# CH32V303RCT6-R1.net
KiCad netlist of a schematic drawn in Altium Designer
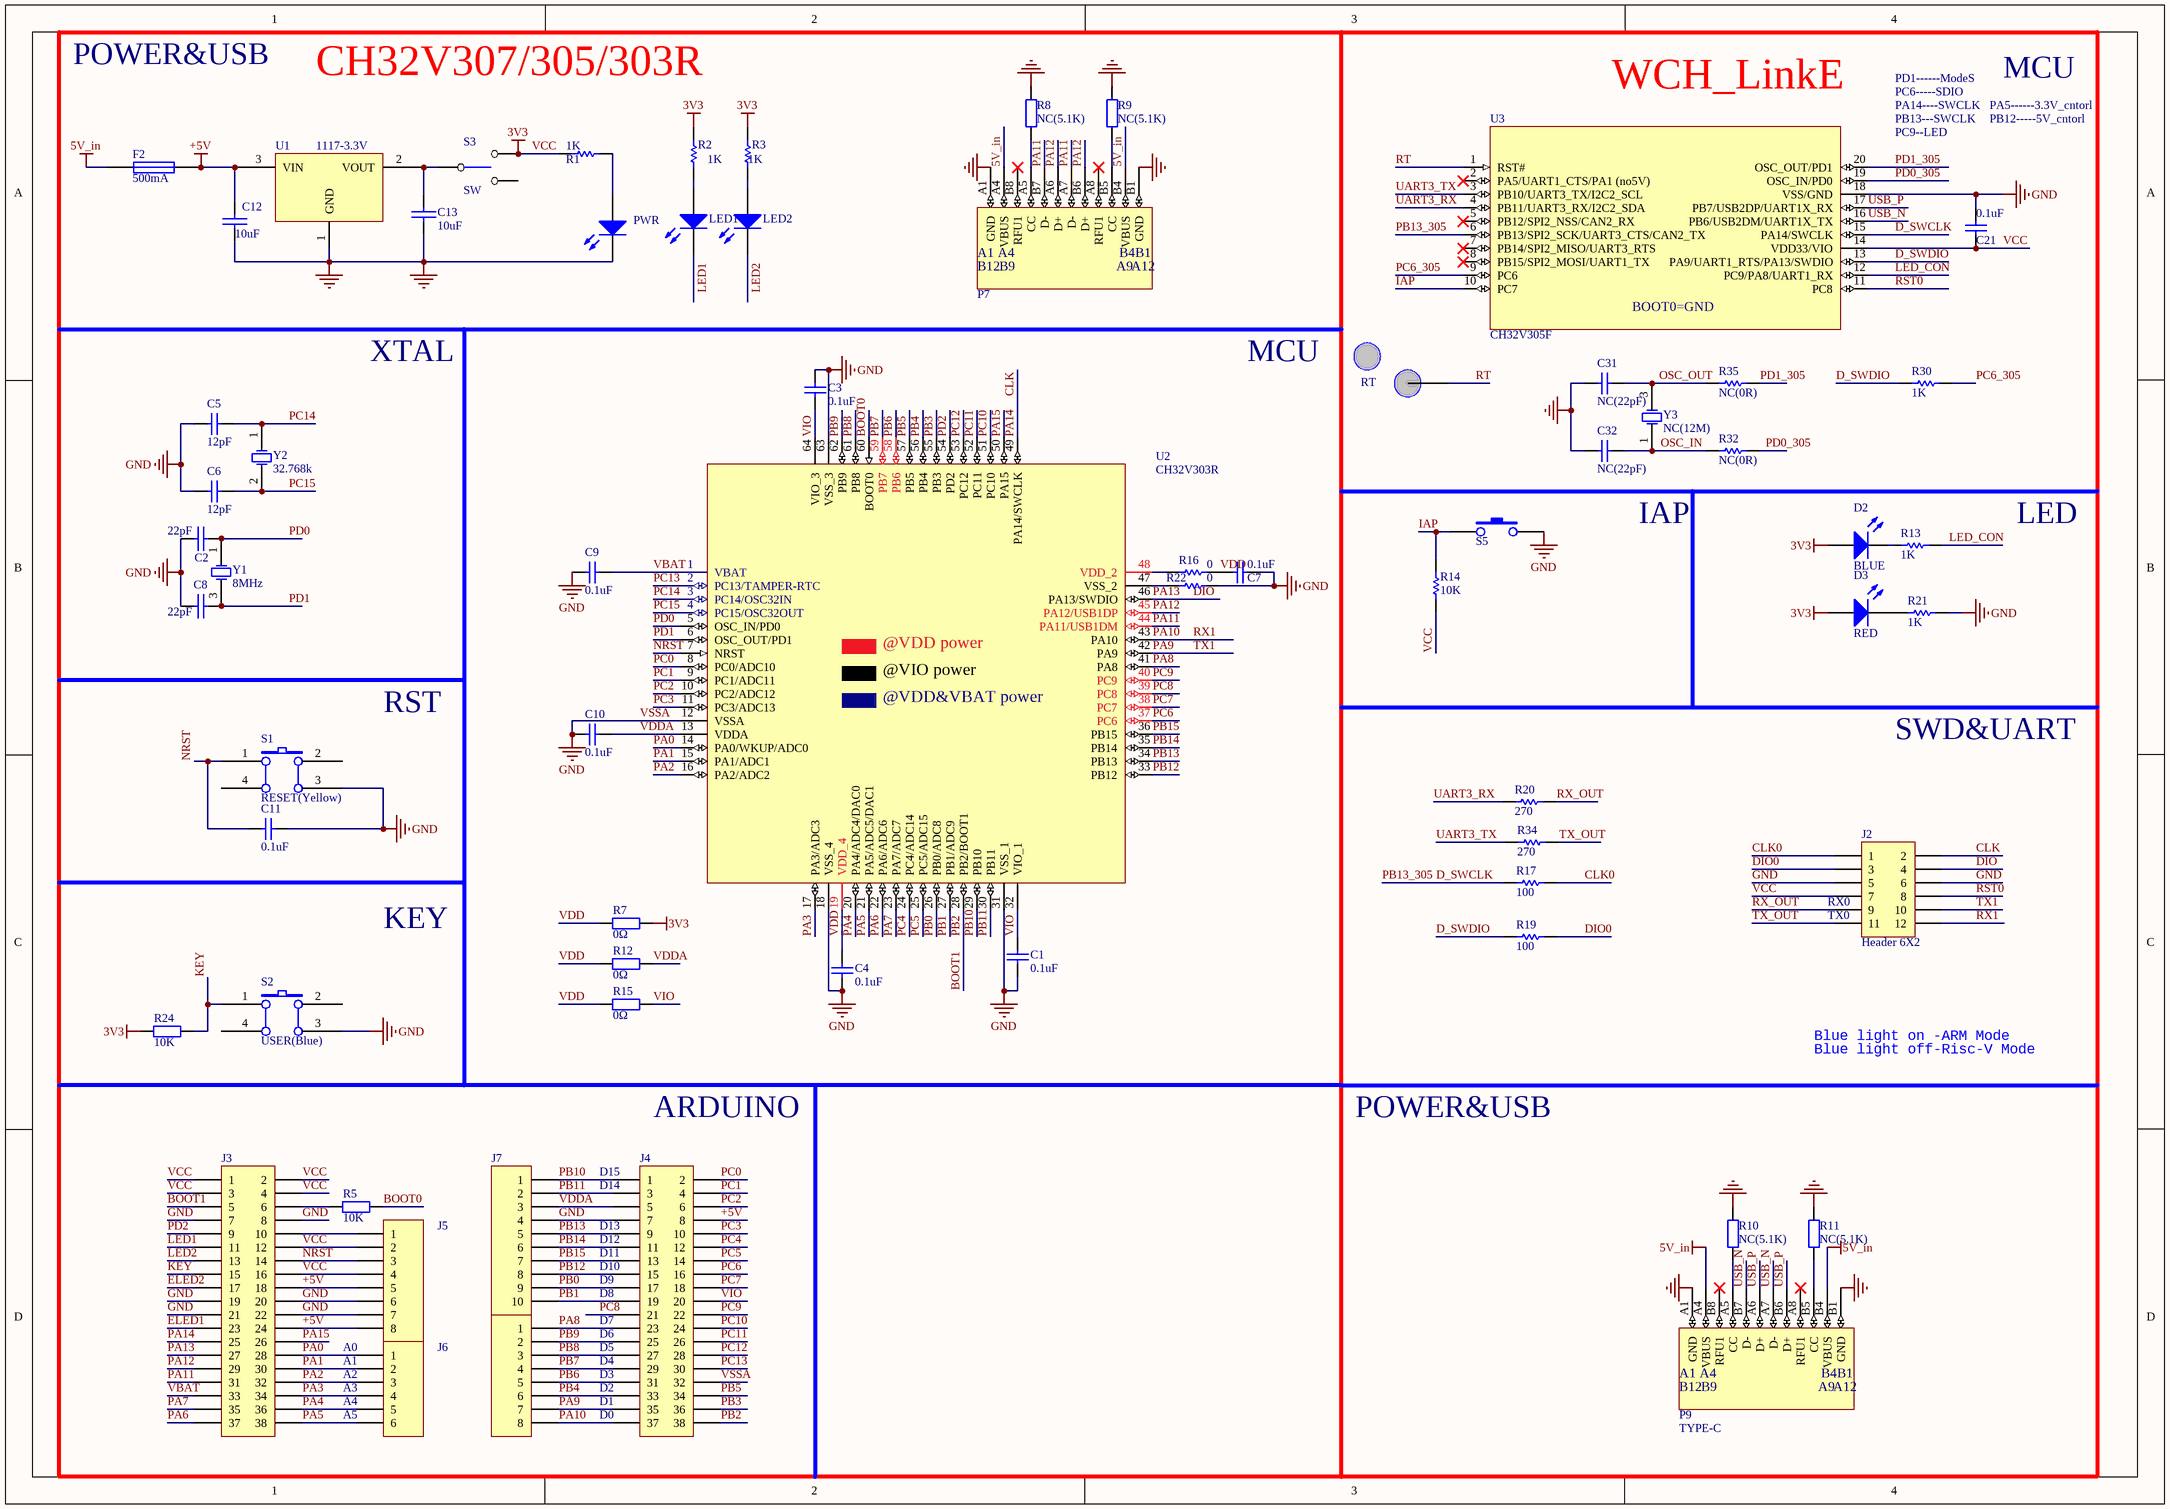
[diagram p0: CH32V303RCT6-R1.SchDoc]

(export (version "E")
  (design (tool "Eeschema 10.0.6"))
  (components
    (comp (ref "C1")
      (value "0.1uF")
      (footprint "0603_C")
      (description "Capacitor")
      (libsource (lib "Miscellaneous Devices") (part "Cap"))
    )
    (comp (ref "C2")
      (value "22pF")
      (footprint "0603_C")
      (description "Capacitor")
      (libsource (lib "*") (part "CAP"))
    )
    (comp (ref "C3")
      (value "0.1uF")
      (footprint "0603_C")
      (description "Capacitor")
      (libsource (lib "Miscellaneous Devices") (part "Cap"))
    )
    (comp (ref "C4")
      (value "0.1uF")
      (footprint "0603_C")
      (description "Capacitor")
      (libsource (lib "Miscellaneous Devices") (part "Cap"))
    )
    (comp (ref "C5")
      (value "12pF")
      (footprint "0603_C")
      (description "Capacitor")
      (libsource (lib "Miscellaneous Devices") (part "Cap"))
    )
    (comp (ref "C6")
      (value "12pF")
      (footprint "0603_C")
      (description "Capacitor")
      (libsource (lib "Miscellaneous Devices") (part "Cap"))
    )
    (comp (ref "C7")
      (value "0.1uF")
      (footprint "0603_C")
      (description "Capacitor")
      (libsource (lib "Miscellaneous Devices") (part "Cap"))
    )
    (comp (ref "C8")
      (value "22pF")
      (footprint "0603_C")
      (description "Capacitor")
      (libsource (lib "*") (part "CAP"))
    )
    (comp (ref "C9")
      (value "0.1uF")
      (footprint "0603_C")
      (description "Capacitor")
      (libsource (lib "Miscellaneous Devices") (part "Cap"))
    )
    (comp (ref "C10")
      (value "0.1uF")
      (footprint "0603_C")
      (description "Capacitor")
      (libsource (lib "Miscellaneous Devices") (part "Cap"))
    )
    (comp (ref "C11")
      (value "0.1uF")
      (footprint "0603_C")
      (description "Capacitor")
      (libsource (lib "Miscellaneous Devices") (part "Cap"))
    )
    (comp (ref "C12")
      (value "10uF")
      (footprint "3216_C")
      (description "Capacitor")
      (libsource (lib "*") (part "CAP"))
    )
    (comp (ref "C13")
      (value "10uF")
      (footprint "3216_C")
      (description "Capacitor")
      (libsource (lib "*") (part "CAP"))
    )
    (comp (ref "C21")
      (value "0.1uF")
      (footprint "0603_C")
      (description "Capacitor")
      (libsource (lib "Miscellaneous Devices") (part "Cap"))
    )
    (comp (ref "C31")
      (value "NC(22pF)")
      (footprint "0603_C")
      (description "Capacitor")
      (fields (field (name "PUBLISHER") "Altium Limited"))
      (libsource (lib "*") (part "Cap"))
    )
    (comp (ref "C32")
      (value "NC(22pF)")
      (footprint "0603_C")
      (description "Capacitor")
      (fields (field (name "PUBLISHER") "Altium Limited"))
      (libsource (lib "*") (part "Cap"))
    )
    (comp (ref "D2")
      (value "BLUE")
      (footprint "0603+")
      (description "Typical RED, GREEN, YELLOW, AMBER GaAs LED")
      (fields (field (name "PUBLISHER") "Altium Limited"))
      (libsource (lib "MYLIB") (part "D0603"))
    )
    (comp (ref "D3")
      (value "RED")
      (footprint "0603+")
      (description "Typical RED, GREEN, YELLOW, AMBER GaAs LED")
      (fields (field (name "PUBLISHER") "Altium Limited"))
      (libsource (lib "MYLIB") (part "D0603"))
    )
    (comp (ref "F2")
      (value "500mA")
      (footprint "0805")
      (description "Fuse")
      (libsource (lib "*") (part "FUSE1"))
    )
    (comp (ref "J2")
      (value "Header 6X2")
      (footprint "IDC12-2.54mm")
      (description "Header, 6-Pin, Dual row")
      (fields (field (name "PUBLISHER") "Altium Limited"))
      (libsource (lib "Miscellaneous Connectors") (part "Header 6X2"))
    )
    (comp (ref "J3")
      (value "Header 19X2")
      (footprint "IDC38-2.54mm")
      (description "Header, 19-Pin, Dual row")
      (fields (field (name "PUBLISHER") "Altium Limited"))
      (libsource (lib "Miscellaneous Connectors") (part "Header 19X2"))
    )
    (comp (ref "J4")
      (value "Header 19X2")
      (footprint "IDC38-2.54mm")
      (description "Header, 19-Pin, Dual row")
      (fields (field (name "PUBLISHER") "Altium Limited"))
      (libsource (lib "Miscellaneous Connectors") (part "Header 19X2"))
    )
    (comp (ref "J5")
      (value "Header 8")
      (footprint "SIP8-2.54mm")
      (description "Header, 8-Pin")
      (fields (field (name "PUBLISHER") "Altium Limited"))
      (libsource (lib "") (part "Header 8_1"))
    )
    (comp (ref "J6")
      (value "Header 6")
      (footprint "SIP6-2.54MM")
      (description "Header, 6-Pin")
      (fields (field (name "PUBLISHER") "Altium Limited"))
      (libsource (lib "Miscellaneous Connectors") (part "Header 6"))
    )
    (comp (ref "J7")
      (value "Header 10")
      (footprint "SIP10-2.54mm")
      (description "Header, 10-Pin")
      (fields (field (name "PUBLISHER") "Altium Limited"))
      (libsource (lib "Miscellaneous Connectors") (part "Header 10"))
    )
    (comp (ref "J8")
      (value "Header 8")
      (footprint "SIP8-2.54mm")
      (description "Header, 8-Pin")
      (fields (field (name "PUBLISHER") "Altium Limited"))
      (libsource (lib "Miscellaneous Connectors") (part "Header 8"))
    )
    (comp (ref "LED1")
      (value "LED1   blue")
      (footprint "0603+")
      (description "Typical INFRARED GaAs LED")
      (fields (field (name "PUBLISHER") "Altium Limited"))
      (libsource (lib "Miscellaneous Devices") (part "LED0"))
    )
    (comp (ref "LED2")
      (value "LED2  blue")
      (footprint "0603+")
      (description "Typical INFRARED GaAs LED")
      (fields (field (name "PUBLISHER") "Altium Limited"))
      (libsource (lib "Miscellaneous Devices") (part "LED0"))
    )
    (comp (ref "P7")
      (value "TYPE-C")
      (footprint "TYPE-C-Receptacle-2.0")
      (libsource (lib "*") (part "TYPE-C1"))
    )
    (comp (ref "P9")
      (value "TYPE-C")
      (footprint "TYPE-C-Receptacle-2.0")
      (libsource (lib "*") (part "TYPE-C1"))
    )
    (comp (ref "PWR")
      (value "POWER  red")
      (footprint "0603+")
      (description "Typical INFRARED GaAs LED")
      (fields (field (name "PUBLISHER") "Altium Limited"))
      (libsource (lib "Miscellaneous Devices") (part "LED0"))
    )
    (comp (ref "R1")
      (value "1K")
      (footprint "0603")
      (description "Semiconductor Resistor")
      (libsource (lib "Miscellaneous Devices") (part "Res Semi"))
    )
    (comp (ref "R2")
      (value "1K")
      (footprint "0603")
      (description "Semiconductor Resistor")
      (libsource (lib "Miscellaneous Devices") (part "Res Semi"))
    )
    (comp (ref "R3")
      (value "1K")
      (footprint "0603")
      (description "Semiconductor Resistor")
      (libsource (lib "Miscellaneous Devices") (part "Res Semi"))
    )
    (comp (ref "R5")
      (value "10K")
      (footprint "0603")
      (description "Resistor")
      (libsource (lib "") (part "Res2_1"))
    )
    (comp (ref "R7")
      (value "0Ω")
      (footprint "0603")
      (description "Resistor")
      (libsource (lib "") (part "Res2_2"))
    )
    (comp (ref "R8")
      (value "NC(5.1K)")
      (footprint "0603")
      (description "Resistor")
      (libsource (lib "") (part "Res2_3"))
    )
    (comp (ref "R9")
      (value "NC(5.1K)")
      (footprint "0603")
      (description "Resistor")
      (libsource (lib "") (part "Res2_3"))
    )
    (comp (ref "R10")
      (value "NC(5.1K)")
      (footprint "0603")
      (description "Resistor")
      (libsource (lib "Miscellaneous Devices") (part "Res2"))
    )
    (comp (ref "R11")
      (value "NC(5.1K)")
      (footprint "0603")
      (description "Resistor")
      (libsource (lib "Miscellaneous Devices") (part "Res2"))
    )
    (comp (ref "R12")
      (value "0Ω")
      (footprint "0603")
      (description "Resistor")
      (libsource (lib "") (part "Res2_2"))
    )
    (comp (ref "R13")
      (value "1K")
      (footprint "0603")
      (description "Resistor")
      (fields (field (name "PUBLISHER") "Altium Limited"))
      (libsource (lib "MYLIB") (part "0603-1"))
    )
    (comp (ref "R14")
      (value "10K")
      (footprint "0603")
      (description "Resistor")
      (fields (field (name "PUBLISHER") "Altium Limited"))
      (libsource (lib "MYLIB") (part "0603-1"))
    )
    (comp (ref "R15")
      (value "0Ω")
      (footprint "0603")
      (description "Resistor")
      (libsource (lib "") (part "Res2_2"))
    )
    (comp (ref "R16")
      (value "0")
      (footprint "0603")
      (description "Resistor")
      (fields (field (name "PUBLISHER") "Altium Limited"))
      (libsource (lib "MYLIB") (part "0603-1"))
    )
    (comp (ref "R17")
      (value "100")
      (footprint "0603")
      (description "Resistor")
      (fields (field (name "PUBLISHER") "Altium Limited"))
      (libsource (lib "MYLIB") (part "0603-1"))
    )
    (comp (ref "R19")
      (value "100")
      (footprint "0603")
      (description "Resistor")
      (fields (field (name "PUBLISHER") "Altium Limited"))
      (libsource (lib "MYLIB") (part "0603-1"))
    )
    (comp (ref "R20")
      (value "270")
      (footprint "0603")
      (description "Resistor")
      (fields (field (name "PUBLISHER") "Altium Limited"))
      (libsource (lib "MYLIB") (part "0603-1"))
    )
    (comp (ref "R21")
      (value "1K")
      (footprint "0603")
      (description "Resistor")
      (fields (field (name "PUBLISHER") "Altium Limited"))
      (libsource (lib "MYLIB") (part "0603-1"))
    )
    (comp (ref "R22")
      (value "0")
      (footprint "0603")
      (description "Resistor")
      (fields (field (name "PUBLISHER") "Altium Limited"))
      (libsource (lib "MYLIB") (part "0603-1"))
    )
    (comp (ref "R24")
      (value "10K")
      (footprint "0603")
      (description "Resistor")
      (libsource (lib "") (part "Res2_2"))
    )
    (comp (ref "R30")
      (value "1K")
      (footprint "0603")
      (description "Resistor")
      (fields (field (name "PUBLISHER") "Altium Limited"))
      (libsource (lib "MYLIB") (part "0603-1"))
    )
    (comp (ref "R32")
      (value "NC(0R)")
      (footprint "0603")
      (description "Resistor")
      (fields (field (name "PUBLISHER") "Altium Limited"))
      (libsource (lib "MYLIB") (part "0603-1"))
    )
    (comp (ref "R34")
      (value "270")
      (footprint "0603")
      (description "Resistor")
      (fields (field (name "PUBLISHER") "Altium Limited"))
      (libsource (lib "MYLIB") (part "0603-1"))
    )
    (comp (ref "R35")
      (value "NC(0R)")
      (footprint "0603")
      (description "Resistor")
      (fields (field (name "PUBLISHER") "Altium Limited"))
      (libsource (lib "MYLIB") (part "0603-1"))
    )
    (comp (ref "RT")
      (value "Testpoint")
      (footprint "TESTPOINT1")
      (description "测试点")
      (libsource (lib "wch_sch_others") (part "Testpoint"))
    )
    (comp (ref "S1")
      (value "RESET(Yellow)")
      (footprint "KEYX")
      (description "SE PUSHBUTTON")
      (libsource (lib "Documents") (part "SW PUSHBUTTON"))
    )
    (comp (ref "S2")
      (value "USER(Blue)")
      (footprint "KEYX")
      (description "SE PUSHBUTTON")
      (libsource (lib "Documents") (part "SW PUSHBUTTON"))
    )
    (comp (ref "S3") (value "SW") (footprint "SW1") (libsource (lib "MYSCH") (part "SW")))
    (comp (ref "S5") (value "KEY") (footprint "贴片按键") (libsource (lib "*") (part "KEY")))
    (comp (ref "U1")
      (value "1117-3.3V")
      (footprint "SOT-223")
      (libsource (lib "wch_sch_others") (part "1117-3.3V"))
    )
    (comp (ref "U2")
      (value "CH32V303R")
      (footprint "LQFP64M_10x10")
      (description "RISC-V FPU HD-MCU, 144MHz, 8*UART, 10*Timer, 4*OPA")
      (libsource (lib "CHXXX") (part "CH32V303R"))
    )
    (comp (ref "U3")
      (value "CH32V305F")
      (footprint "TSSOP20")
      (description "RISC-V FPU HD-MCU, 144MHz, USB_480M, CAN, UART*2, SPI")
      (libsource (lib "CHXXX") (part "CH32V305F"))
    )
    (comp (ref "Y1")
      (value "8MHz")
      (footprint "XT3225")
      (description "Crystal Oscillator")
      (fields (field (name "PUBLISHER") "Altium Limited"))
      (libsource (lib "*") (part "XTAL"))
    )
    (comp (ref "Y2")
      (value "32.768k")
      (footprint "FC-135")
      (description "Crystal Oscillator")
      (fields (field (name "PUBLISHER") "Altium Limited"))
      (libsource (lib "Miscellaneous Devices") (part "XTAL"))
    )
    (comp (ref "Y3")
      (value "NC(12M)")
      (footprint "XT3225")
      (description "Crystal Oscillator")
      (libsource (lib "*") (part "XTAL"))
    )
  )
  (nets
    (net (code "1") (name "+5V") (class "Default")
      (node (ref "C12") (pin "1") (pinfunction "1_1") (pintype "passive"))
      (node (ref "F2") (pin "2") (pinfunction "2_2") (pintype "passive"))
      (node (ref "J3") (pin "18") (pinfunction "18_18") (pintype "passive"))
      (node (ref "J3") (pin "24") (pinfunction "24_24") (pintype "passive"))
      (node (ref "J4") (pin "8") (pinfunction "8_8") (pintype "passive"))
      (node (ref "J5") (pin "5") (pinfunction "5_5") (pintype "passive"))
      (node (ref "J5") (pin "8") (pinfunction "8_8") (pintype "passive"))
      (node (ref "U1") (pin "3") (pinfunction "VIN_3") (pintype "passive"))
    )
    (net (code "2") (name "/BOOT0") (class "Default")
      (node (ref "R5") (pin "2") (pinfunction "2_2") (pintype "passive"))
      (node (ref "U2") (pin "60") (pinfunction "BOOT0_60") (pintype "input"))
    )
    (net (code "3") (name "/BOOT1") (class "Default")
      (node (ref "J3") (pin "5") (pinfunction "5_5") (pintype "passive"))
      (node (ref "J4") (pin "38") (pinfunction "38_38") (pintype "passive"))
      (node (ref "U2") (pin "28") (pinfunction "PB2/BOOT1_28") (pintype "bidirectional"))
    )
    (net (code "4") (name "/CLK") (class "Default")
      (node (ref "J2") (pin "2") (pinfunction "2_2") (pintype "passive"))
      (node (ref "J3") (pin "25") (pinfunction "25_25") (pintype "passive"))
      (node (ref "U2") (pin "49") (pinfunction "PA14/SWCLK_49") (pintype "bidirectional"))
    )
    (net (code "5") (name "/CLK0") (class "Default")
      (node (ref "J2") (pin "1") (pinfunction "1_1") (pintype "passive"))
      (node (ref "R17") (pin "1") (pinfunction "1_1") (pintype "passive"))
    )
    (net (code "6") (name "/DIO") (class "Default")
      (node (ref "J2") (pin "4") (pinfunction "4_4") (pintype "passive"))
      (node (ref "J3") (pin "27") (pinfunction "27_27") (pintype "passive"))
      (node (ref "U2") (pin "46") (pinfunction "PA13/SWDIO_46") (pintype "bidirectional"))
    )
    (net (code "7") (name "/DIO0") (class "Default")
      (node (ref "J2") (pin "3") (pinfunction "3_3") (pintype "passive"))
      (node (ref "R19") (pin "1") (pinfunction "1_1") (pintype "passive"))
    )
    (net (code "8") (name "/D_SWCLK") (class "Default")
      (node (ref "R17") (pin "2") (pinfunction "2_2") (pintype "passive"))
      (node (ref "U3") (pin "15") (pinfunction "PA14/SWCLK_15") (pintype "bidirectional"))
      (node (ref "U3") (pin "6") (pinfunction "PB13/SPI2_SCK/UART3_CTS/CAN2_TX_6") (pintype "bidirectional"))
    )
    (net (code "9") (name "/D_SWDIO") (class "Default")
      (node (ref "R19") (pin "2") (pinfunction "2_2") (pintype "passive"))
      (node (ref "R30") (pin "1") (pinfunction "1_1") (pintype "passive"))
      (node (ref "U3") (pin "13") (pinfunction "PA9/UART1_RTS/PA13/SWDIO_13") (pintype "bidirectional"))
    )
    (net (code "10") (name "/ELED1") (class "Default")
      (node (ref "J3") (pin "23") (pinfunction "23_23") (pintype "passive"))
    )
    (net (code "11") (name "/ELED2") (class "Default")
      (node (ref "J3") (pin "17") (pinfunction "17_17") (pintype "passive"))
    )
    (net (code "12") (name "/IAP") (class "Default")
      (node (ref "R14") (pin "1") (pinfunction "1_1") (pintype "passive"))
      (node (ref "S5") (pin "1") (pinfunction "1_1") (pintype "passive"))
      (node (ref "U3") (pin "10") (pinfunction "PC7_10") (pintype "bidirectional"))
    )
    (net (code "13") (name "/KEY") (class "Default")
      (node (ref "J3") (pin "15") (pinfunction "15_15") (pintype "passive"))
      (node (ref "R24") (pin "1") (pinfunction "1_1") (pintype "passive"))
      (node (ref "S2") (pin "1") (pinfunction "A0_1") (pintype "passive"))
    )
    (net (code "14") (name "/LED1") (class "Default")
      (node (ref "J3") (pin "11") (pinfunction "11_11") (pintype "passive"))
      (node (ref "LED1") (pin "2") (pinfunction "K_2") (pintype "passive"))
    )
    (net (code "15") (name "/LED2") (class "Default")
      (node (ref "J3") (pin "13") (pinfunction "13_13") (pintype "passive"))
      (node (ref "LED2") (pin "2") (pinfunction "K_2") (pintype "passive"))
    )
    (net (code "16") (name "/LED_CON") (class "Default")
      (node (ref "R13") (pin "1") (pinfunction "1_1") (pintype "passive"))
      (node (ref "U3") (pin "12") (pinfunction "PC9/PA8/UART1_RX_12") (pintype "bidirectional"))
    )
    (net (code "17") (name "/NRST") (class "Default")
      (node (ref "C11") (pin "2") (pinfunction "2_2") (pintype "passive"))
      (node (ref "J3") (pin "14") (pinfunction "14_14") (pintype "passive"))
      (node (ref "J5") (pin "3") (pinfunction "3_3") (pintype "passive"))
      (node (ref "S1") (pin "1") (pinfunction "A0_1") (pintype "passive"))
      (node (ref "U2") (pin "7") (pinfunction "NRST_7") (pintype "input"))
    )
    (net (code "18") (name "/OSC_IN") (class "Default")
      (node (ref "C32") (pin "2") (pinfunction "2_2") (pintype "passive"))
      (node (ref "R32") (pin "2") (pinfunction "2_2") (pintype "passive"))
      (node (ref "Y3") (pin "1") (pinfunction "OSC1_1") (pintype "passive"))
    )
    (net (code "19") (name "/OSC_OUT") (class "Default")
      (node (ref "C31") (pin "2") (pinfunction "2_2") (pintype "passive"))
      (node (ref "R35") (pin "2") (pinfunction "2_2") (pintype "passive"))
      (node (ref "Y3") (pin "3") (pinfunction "OSC2_3") (pintype "passive"))
    )
    (net (code "20") (name "/PA0") (class "Default")
      (node (ref "J3") (pin "28") (pinfunction "28_28") (pintype "passive"))
      (node (ref "J6") (pin "1") (pinfunction "1_1") (pintype "passive"))
      (node (ref "U2") (pin "14") (pinfunction "PA0/WKUP/ADC0_14") (pintype "bidirectional"))
    )
    (net (code "21") (name "/PA1") (class "Default")
      (node (ref "J3") (pin "30") (pinfunction "30_30") (pintype "passive"))
      (node (ref "J6") (pin "2") (pinfunction "2_2") (pintype "passive"))
      (node (ref "U2") (pin "15") (pinfunction "PA1/ADC1_15") (pintype "bidirectional"))
    )
    (net (code "22") (name "/PA2") (class "Default")
      (node (ref "J3") (pin "32") (pinfunction "32_32") (pintype "passive"))
      (node (ref "J6") (pin "3") (pinfunction "3_3") (pintype "passive"))
      (node (ref "U2") (pin "16") (pinfunction "PA2/ADC2_16") (pintype "bidirectional"))
    )
    (net (code "23") (name "/PA3") (class "Default")
      (node (ref "J3") (pin "34") (pinfunction "34_34") (pintype "passive"))
      (node (ref "J6") (pin "4") (pinfunction "4_4") (pintype "passive"))
      (node (ref "U2") (pin "17") (pinfunction "PA3/ADC3_17") (pintype "bidirectional"))
    )
    (net (code "24") (name "/PA4") (class "Default")
      (node (ref "J3") (pin "36") (pinfunction "36_36") (pintype "passive"))
      (node (ref "J6") (pin "5") (pinfunction "5_5") (pintype "passive"))
      (node (ref "U2") (pin "20") (pinfunction "PA4/ADC4/DAC0_20") (pintype "bidirectional"))
    )
    (net (code "25") (name "/PA5") (class "Default")
      (node (ref "J3") (pin "38") (pinfunction "38_38") (pintype "passive"))
      (node (ref "J6") (pin "6") (pinfunction "6_6") (pintype "passive"))
      (node (ref "U2") (pin "21") (pinfunction "PA5/ADC5/DAC1_21") (pintype "bidirectional"))
    )
    (net (code "26") (name "/PA6") (class "Default")
      (node (ref "J3") (pin "37") (pinfunction "37_37") (pintype "passive"))
      (node (ref "U2") (pin "22") (pinfunction "PA6/ADC6_22") (pintype "bidirectional"))
    )
    (net (code "27") (name "/PA7") (class "Default")
      (node (ref "J3") (pin "35") (pinfunction "35_35") (pintype "passive"))
      (node (ref "U2") (pin "23") (pinfunction "PA7/ADC7_23") (pintype "bidirectional"))
    )
    (net (code "28") (name "/PA8") (class "Default")
      (node (ref "J4") (pin "23") (pinfunction "23_23") (pintype "passive"))
      (node (ref "J8") (pin "1") (pinfunction "1_1") (pintype "passive"))
      (node (ref "U2") (pin "41") (pinfunction "PA8_41") (pintype "bidirectional"))
    )
    (net (code "29") (name "/PA9") (class "Default")
      (node (ref "J2") (pin "10") (pinfunction "10_10") (pintype "passive"))
      (node (ref "J4") (pin "35") (pinfunction "35_35") (pintype "passive"))
      (node (ref "J8") (pin "7") (pinfunction "7_7") (pintype "passive"))
      (node (ref "U2") (pin "42") (pinfunction "PA9_42") (pintype "bidirectional"))
    )
    (net (code "30") (name "/PA10") (class "Default")
      (node (ref "J2") (pin "12") (pinfunction "12_12") (pintype "passive"))
      (node (ref "J4") (pin "37") (pinfunction "37_37") (pintype "passive"))
      (node (ref "J8") (pin "8") (pinfunction "8_8") (pintype "passive"))
      (node (ref "U2") (pin "43") (pinfunction "PA10_43") (pintype "bidirectional"))
    )
    (net (code "31") (name "/PA11") (class "Default")
      (node (ref "J3") (pin "31") (pinfunction "31_31") (pintype "passive"))
      (node (ref "P7") (pin "A7") (pinfunction "D-_A7") (pintype "bidirectional"))
      (node (ref "P7") (pin "B7") (pinfunction "D-_B7") (pintype "bidirectional"))
      (node (ref "U2") (pin "44") (pinfunction "PA11/USB1DM_44") (pintype "bidirectional"))
    )
    (net (code "32") (name "/PA12") (class "Default")
      (node (ref "J3") (pin "29") (pinfunction "29_29") (pintype "passive"))
      (node (ref "P7") (pin "A6") (pinfunction "D+_A6") (pintype "bidirectional"))
      (node (ref "P7") (pin "B6") (pinfunction "D+_B6") (pintype "bidirectional"))
      (node (ref "U2") (pin "45") (pinfunction "PA12/USB1DP_45") (pintype "bidirectional"))
    )
    (net (code "33") (name "/PA15") (class "Default")
      (node (ref "J3") (pin "26") (pinfunction "26_26") (pintype "passive"))
      (node (ref "U2") (pin "50") (pinfunction "PA15_50") (pintype "bidirectional"))
    )
    (net (code "34") (name "/PB0") (class "Default")
      (node (ref "J4") (pin "17") (pinfunction "17_17") (pintype "passive"))
      (node (ref "J7") (pin "9") (pinfunction "9_9") (pintype "passive"))
      (node (ref "U2") (pin "26") (pinfunction "PB0/ADC8_26") (pintype "bidirectional"))
    )
    (net (code "35") (name "/PB1") (class "Default")
      (node (ref "J4") (pin "19") (pinfunction "19_19") (pintype "passive"))
      (node (ref "J7") (pin "10") (pinfunction "10_10") (pintype "passive"))
      (node (ref "U2") (pin "27") (pinfunction "PB1/ADC9_27") (pintype "bidirectional"))
    )
    (net (code "36") (name "/PB3") (class "Default")
      (node (ref "J4") (pin "36") (pinfunction "36_36") (pintype "passive"))
      (node (ref "U2") (pin "55") (pinfunction "PB3_55") (pintype "bidirectional"))
    )
    (net (code "37") (name "/PB4") (class "Default")
      (node (ref "J4") (pin "33") (pinfunction "33_33") (pintype "passive"))
      (node (ref "J8") (pin "6") (pinfunction "6_6") (pintype "passive"))
      (node (ref "U2") (pin "56") (pinfunction "PB4_56") (pintype "bidirectional"))
    )
    (net (code "38") (name "/PB5") (class "Default")
      (node (ref "J4") (pin "34") (pinfunction "34_34") (pintype "passive"))
      (node (ref "U2") (pin "57") (pinfunction "PB5_57") (pintype "bidirectional"))
    )
    (net (code "39") (name "/PB6") (class "Default")
      (node (ref "J4") (pin "31") (pinfunction "31_31") (pintype "passive"))
      (node (ref "J8") (pin "5") (pinfunction "5_5") (pintype "passive"))
      (node (ref "U2") (pin "58") (pinfunction "PB6_58") (pintype "bidirectional"))
    )
    (net (code "40") (name "/PB7") (class "Default")
      (node (ref "J4") (pin "29") (pinfunction "29_29") (pintype "passive"))
      (node (ref "J8") (pin "4") (pinfunction "4_4") (pintype "passive"))
      (node (ref "U2") (pin "59") (pinfunction "PB7_59") (pintype "bidirectional"))
    )
    (net (code "41") (name "/PB8") (class "Default")
      (node (ref "J4") (pin "27") (pinfunction "27_27") (pintype "passive"))
      (node (ref "J8") (pin "3") (pinfunction "3_3") (pintype "passive"))
      (node (ref "U2") (pin "61") (pinfunction "PB8_61") (pintype "bidirectional"))
    )
    (net (code "42") (name "/PB9") (class "Default")
      (node (ref "J4") (pin "25") (pinfunction "25_25") (pintype "passive"))
      (node (ref "J8") (pin "2") (pinfunction "2_2") (pintype "passive"))
      (node (ref "U2") (pin "62") (pinfunction "PB9_62") (pintype "bidirectional"))
    )
    (net (code "43") (name "/PB10") (class "Default")
      (node (ref "J4") (pin "1") (pinfunction "1_1") (pintype "passive"))
      (node (ref "J7") (pin "1") (pinfunction "1_1") (pintype "passive"))
      (node (ref "U2") (pin "29") (pinfunction "PB10_29") (pintype "bidirectional"))
    )
    (net (code "44") (name "/PB11") (class "Default")
      (node (ref "J4") (pin "3") (pinfunction "3_3") (pintype "passive"))
      (node (ref "J7") (pin "2") (pinfunction "2_2") (pintype "passive"))
      (node (ref "U2") (pin "30") (pinfunction "PB11_30") (pintype "bidirectional"))
    )
    (net (code "45") (name "/PB12") (class "Default")
      (node (ref "J4") (pin "15") (pinfunction "15_15") (pintype "passive"))
      (node (ref "J7") (pin "8") (pinfunction "8_8") (pintype "passive"))
      (node (ref "U2") (pin "33") (pinfunction "PB12_33") (pintype "bidirectional"))
    )
    (net (code "46") (name "/PB13") (class "Default")
      (node (ref "J4") (pin "9") (pinfunction "9_9") (pintype "passive"))
      (node (ref "J7") (pin "5") (pinfunction "5_5") (pintype "passive"))
      (node (ref "U2") (pin "34") (pinfunction "PB13_34") (pintype "bidirectional"))
    )
    (net (code "47") (name "/PB14") (class "Default")
      (node (ref "J4") (pin "11") (pinfunction "11_11") (pintype "passive"))
      (node (ref "J7") (pin "6") (pinfunction "6_6") (pintype "passive"))
      (node (ref "U2") (pin "35") (pinfunction "PB14_35") (pintype "bidirectional"))
    )
    (net (code "48") (name "/PB15") (class "Default")
      (node (ref "J4") (pin "13") (pinfunction "13_13") (pintype "passive"))
      (node (ref "J7") (pin "7") (pinfunction "7_7") (pintype "passive"))
      (node (ref "U2") (pin "36") (pinfunction "PB15_36") (pintype "bidirectional"))
    )
    (net (code "49") (name "/PC0") (class "Default")
      (node (ref "J4") (pin "2") (pinfunction "2_2") (pintype "passive"))
      (node (ref "U2") (pin "8") (pinfunction "PC0/ADC10_8") (pintype "bidirectional"))
    )
    (net (code "50") (name "/PC1") (class "Default")
      (node (ref "J4") (pin "4") (pinfunction "4_4") (pintype "passive"))
      (node (ref "U2") (pin "9") (pinfunction "PC1/ADC11_9") (pintype "bidirectional"))
    )
    (net (code "51") (name "/PC2") (class "Default")
      (node (ref "J4") (pin "6") (pinfunction "6_6") (pintype "passive"))
      (node (ref "U2") (pin "10") (pinfunction "PC2/ADC12_10") (pintype "bidirectional"))
    )
    (net (code "52") (name "/PC3") (class "Default")
      (node (ref "J4") (pin "10") (pinfunction "10_10") (pintype "passive"))
      (node (ref "U2") (pin "11") (pinfunction "PC3/ADC13_11") (pintype "bidirectional"))
    )
    (net (code "53") (name "/PC4") (class "Default")
      (node (ref "J4") (pin "12") (pinfunction "12_12") (pintype "passive"))
      (node (ref "U2") (pin "24") (pinfunction "PC4/ADC14_24") (pintype "bidirectional"))
    )
    (net (code "54") (name "/PC5") (class "Default")
      (node (ref "J4") (pin "14") (pinfunction "14_14") (pintype "passive"))
      (node (ref "U2") (pin "25") (pinfunction "PC5/ADC15_25") (pintype "bidirectional"))
    )
    (net (code "55") (name "/PC6") (class "Default")
      (node (ref "J4") (pin "16") (pinfunction "16_16") (pintype "passive"))
      (node (ref "U2") (pin "37") (pinfunction "PC6_37") (pintype "bidirectional"))
    )
    (net (code "56") (name "/PC6_305") (class "Default")
      (node (ref "R30") (pin "2") (pinfunction "2_2") (pintype "passive"))
      (node (ref "U3") (pin "9") (pinfunction "PC6_9") (pintype "bidirectional"))
    )
    (net (code "57") (name "/PC7") (class "Default")
      (node (ref "J4") (pin "18") (pinfunction "18_18") (pintype "passive"))
      (node (ref "U2") (pin "38") (pinfunction "PC7_38") (pintype "bidirectional"))
    )
    (net (code "58") (name "/PC8") (class "Default")
      (node (ref "J4") (pin "21") (pinfunction "21_21") (pintype "passive"))
      (node (ref "U2") (pin "39") (pinfunction "PC8_39") (pintype "bidirectional"))
    )
    (net (code "59") (name "/PC9") (class "Default")
      (node (ref "J4") (pin "22") (pinfunction "22_22") (pintype "passive"))
      (node (ref "U2") (pin "40") (pinfunction "PC9_40") (pintype "bidirectional"))
    )
    (net (code "60") (name "/PC10") (class "Default")
      (node (ref "J4") (pin "24") (pinfunction "24_24") (pintype "passive"))
      (node (ref "U2") (pin "51") (pinfunction "PC10_51") (pintype "bidirectional"))
    )
    (net (code "61") (name "/PC11") (class "Default")
      (node (ref "J4") (pin "26") (pinfunction "26_26") (pintype "passive"))
      (node (ref "U2") (pin "52") (pinfunction "PC11_52") (pintype "bidirectional"))
    )
    (net (code "62") (name "/PC12") (class "Default")
      (node (ref "J4") (pin "28") (pinfunction "28_28") (pintype "passive"))
      (node (ref "U2") (pin "53") (pinfunction "PC12_53") (pintype "bidirectional"))
    )
    (net (code "63") (name "/PC13") (class "Default")
      (node (ref "J4") (pin "30") (pinfunction "30_30") (pintype "passive"))
      (node (ref "U2") (pin "2") (pinfunction "PC13/TAMPER-RTC_2") (pintype "bidirectional"))
    )
    (net (code "64") (name "/PC14") (class "Default")
      (node (ref "C5") (pin "1") (pinfunction "1_1") (pintype "passive"))
      (node (ref "U2") (pin "3") (pinfunction "PC14/OSC32IN_3") (pintype "bidirectional"))
      (node (ref "Y2") (pin "1") (pinfunction "OSC1_1") (pintype "passive"))
    )
    (net (code "65") (name "/PC15") (class "Default")
      (node (ref "C6") (pin "1") (pinfunction "1_1") (pintype "passive"))
      (node (ref "U2") (pin "4") (pinfunction "PC15/OSC32OUT_4") (pintype "bidirectional"))
      (node (ref "Y2") (pin "2") (pinfunction "OSC2_2") (pintype "passive"))
    )
    (net (code "66") (name "/PD0") (class "Default")
      (node (ref "C2") (pin "2") (pinfunction "2_2") (pintype "passive"))
      (node (ref "U2") (pin "5") (pinfunction "OSC_IN/PD0_5") (pintype "bidirectional"))
      (node (ref "Y1") (pin "1") (pinfunction "OSC1_1") (pintype "passive"))
    )
    (net (code "67") (name "/PD0_305") (class "Default")
      (node (ref "R32") (pin "1") (pinfunction "1_1") (pintype "passive"))
      (node (ref "U3") (pin "19") (pinfunction "OSC_IN/PD0_19") (pintype "bidirectional"))
    )
    (net (code "68") (name "/PD1") (class "Default")
      (node (ref "C8") (pin "2") (pinfunction "2_2") (pintype "passive"))
      (node (ref "U2") (pin "6") (pinfunction "OSC_OUT/PD1_6") (pintype "bidirectional"))
      (node (ref "Y1") (pin "3") (pinfunction "OSC2_3") (pintype "passive"))
    )
    (net (code "69") (name "/PD1_305") (class "Default")
      (node (ref "R35") (pin "1") (pinfunction "1_1") (pintype "passive"))
      (node (ref "U3") (pin "20") (pinfunction "OSC_OUT/PD1_20") (pintype "bidirectional"))
    )
    (net (code "70") (name "/PD2") (class "Default")
      (node (ref "J3") (pin "9") (pinfunction "9_9") (pintype "passive"))
      (node (ref "U2") (pin "54") (pinfunction "PD2_54") (pintype "bidirectional"))
    )
    (net (code "71") (name "/RST0") (class "Default")
      (node (ref "J2") (pin "8") (pinfunction "8_8") (pintype "passive"))
      (node (ref "U3") (pin "11") (pinfunction "PC8_11") (pintype "bidirectional"))
    )
    (net (code "72") (name "/RT") (class "Default")
      (node (ref "RT") (pin "1") (pinfunction "point_1") (pintype "passive"))
      (node (ref "U3") (pin "1") (pinfunction "RST#_1") (pintype "input"))
    )
    (net (code "73") (name "/RX_OUT") (class "Default")
      (node (ref "J2") (pin "9") (pinfunction "9_9") (pintype "passive"))
      (node (ref "R20") (pin "1") (pinfunction "1_1") (pintype "passive"))
    )
    (net (code "74") (name "/TX_OUT") (class "Default")
      (node (ref "J2") (pin "11") (pinfunction "11_11") (pintype "passive"))
      (node (ref "R34") (pin "1") (pinfunction "1_1") (pintype "passive"))
    )
    (net (code "75") (name "/UART3_RX") (class "Default")
      (node (ref "R20") (pin "2") (pinfunction "2_2") (pintype "passive"))
      (node (ref "U3") (pin "4") (pinfunction "PB11/UART3_RX/I2C2_SDA_4") (pintype "bidirectional"))
    )
    (net (code "76") (name "/UART3_TX") (class "Default")
      (node (ref "R34") (pin "2") (pinfunction "2_2") (pintype "passive"))
      (node (ref "U3") (pin "3") (pinfunction "PB10/UART3_TX/I2C2_SCL_3") (pintype "bidirectional"))
    )
    (net (code "77") (name "/USB_N") (class "Default")
      (node (ref "P9") (pin "A7") (pinfunction "D-_A7") (pintype "bidirectional"))
      (node (ref "P9") (pin "B7") (pinfunction "D-_B7") (pintype "bidirectional"))
      (node (ref "U3") (pin "16") (pinfunction "PB6/USB2DM/UART1X_TX_16") (pintype "bidirectional"))
    )
    (net (code "78") (name "/USB_P") (class "Default")
      (node (ref "P9") (pin "A6") (pinfunction "D+_A6") (pintype "bidirectional"))
      (node (ref "P9") (pin "B6") (pinfunction "D+_B6") (pintype "bidirectional"))
      (node (ref "U3") (pin "17") (pinfunction "PB7/USB2DP/UART1X_RX_17") (pintype "bidirectional"))
    )
    (net (code "79") (name "/VBAT") (class "Default")
      (node (ref "C9") (pin "1") (pinfunction "1_1") (pintype "passive"))
      (node (ref "J3") (pin "33") (pinfunction "33_33") (pintype "passive"))
      (node (ref "U2") (pin "1") (pinfunction "VBAT_1") (pintype "power_in"))
    )
    (net (code "80") (name "/VDD") (class "Default")
      (node (ref "C4") (pin "2") (pinfunction "2_2") (pintype "passive"))
      (node (ref "C7") (pin "2") (pinfunction "2_2") (pintype "passive"))
      (node (ref "R12") (pin "2") (pinfunction "2_2") (pintype "passive"))
      (node (ref "R15") (pin "2") (pinfunction "2_2") (pintype "passive"))
      (node (ref "R16") (pin "1") (pinfunction "1_1") (pintype "passive"))
      (node (ref "R7") (pin "2") (pinfunction "2_2") (pintype "passive"))
      (node (ref "U2") (pin "19") (pinfunction "VDD_4_19") (pintype "power_in"))
    )
    (net (code "81") (name "/VDDA") (class "Default")
      (node (ref "C10") (pin "1") (pinfunction "1_1") (pintype "passive"))
      (node (ref "J4") (pin "5") (pinfunction "5_5") (pintype "passive"))
      (node (ref "J7") (pin "3") (pinfunction "3_3") (pintype "passive"))
      (node (ref "R12") (pin "1") (pinfunction "1_1") (pintype "passive"))
      (node (ref "U2") (pin "13") (pinfunction "VDDA_13") (pintype "power_in"))
    )
    (net (code "82") (name "/VIO") (class "Default")
      (node (ref "C1") (pin "2") (pinfunction "2_2") (pintype "passive"))
      (node (ref "C3") (pin "2") (pinfunction "2_2") (pintype "passive"))
      (node (ref "J4") (pin "20") (pinfunction "20_20") (pintype "passive"))
      (node (ref "R15") (pin "1") (pinfunction "1_1") (pintype "passive"))
      (node (ref "U2") (pin "32") (pinfunction "VIO_1_32") (pintype "power_in"))
      (node (ref "U2") (pin "64") (pinfunction "VIO_3_64") (pintype "power_in"))
    )
    (net (code "83") (name "3V3") (class "Default")
      (node (ref "C21") (pin "1") (pinfunction "1_1") (pintype "passive"))
      (node (ref "D2") (pin "1") (pinfunction "A_1") (pintype "passive"))
      (node (ref "D3") (pin "1") (pinfunction "A_1") (pintype "passive"))
      (node (ref "J2") (pin "7") (pinfunction "7_7") (pintype "passive"))
      (node (ref "J3") (pin "1") (pinfunction "1_1") (pintype "passive"))
      (node (ref "J3") (pin "12") (pinfunction "12_12") (pintype "passive"))
      (node (ref "J3") (pin "16") (pinfunction "16_16") (pintype "passive"))
      (node (ref "J3") (pin "2") (pinfunction "2_2") (pintype "passive"))
      (node (ref "J3") (pin "3") (pinfunction "3_3") (pintype "passive"))
      (node (ref "J3") (pin "4") (pinfunction "4_4") (pintype "passive"))
      (node (ref "J5") (pin "2") (pinfunction "2_2") (pintype "passive"))
      (node (ref "J5") (pin "4") (pinfunction "4_4") (pintype "passive"))
      (node (ref "R1") (pin "2") (pinfunction "2_2") (pintype "passive"))
      (node (ref "R14") (pin "2") (pinfunction "2_2") (pintype "passive"))
      (node (ref "R2") (pin "1") (pinfunction "1_1") (pintype "passive"))
      (node (ref "R24") (pin "2") (pinfunction "2_2") (pintype "passive"))
      (node (ref "R3") (pin "1") (pinfunction "1_1") (pintype "passive"))
      (node (ref "R7") (pin "1") (pinfunction "1_1") (pintype "passive"))
      (node (ref "S3") (pin "3") (pinfunction "3_3") (pintype "passive"))
      (node (ref "U3") (pin "14") (pinfunction "VDD33/VIO_14") (pintype "power_in"))
    )
    (net (code "84") (name "5V_in") (class "Default")
      (node (ref "F2") (pin "1") (pinfunction "1_1") (pintype "passive"))
      (node (ref "P7") (pin "A4") (pinfunction "VBUS_A4") (pintype "bidirectional"))
      (node (ref "P7") (pin "B4") (pinfunction "VBUS_B4") (pintype "bidirectional"))
      (node (ref "P9") (pin "A4") (pinfunction "VBUS_A4") (pintype "bidirectional"))
      (node (ref "P9") (pin "B4") (pinfunction "VBUS_B4") (pintype "bidirectional"))
    )
    (net (code "85") (name "GND") (class "Default")
      (node (ref "C1") (pin "1") (pinfunction "1_1") (pintype "passive"))
      (node (ref "C10") (pin "2") (pinfunction "2_2") (pintype "passive"))
      (node (ref "C11") (pin "1") (pinfunction "1_1") (pintype "passive"))
      (node (ref "C12") (pin "2") (pinfunction "2_2") (pintype "passive"))
      (node (ref "C13") (pin "2") (pinfunction "2_2") (pintype "passive"))
      (node (ref "C2") (pin "1") (pinfunction "1_1") (pintype "passive"))
      (node (ref "C21") (pin "2") (pinfunction "2_2") (pintype "passive"))
      (node (ref "C3") (pin "1") (pinfunction "1_1") (pintype "passive"))
      (node (ref "C31") (pin "1") (pinfunction "1_1") (pintype "passive"))
      (node (ref "C32") (pin "1") (pinfunction "1_1") (pintype "passive"))
      (node (ref "C4") (pin "1") (pinfunction "1_1") (pintype "passive"))
      (node (ref "C5") (pin "2") (pinfunction "2_2") (pintype "passive"))
      (node (ref "C6") (pin "2") (pinfunction "2_2") (pintype "passive"))
      (node (ref "C7") (pin "1") (pinfunction "1_1") (pintype "passive"))
      (node (ref "C8") (pin "1") (pinfunction "1_1") (pintype "passive"))
      (node (ref "C9") (pin "2") (pinfunction "2_2") (pintype "passive"))
      (node (ref "J2") (pin "5") (pinfunction "5_5") (pintype "passive"))
      (node (ref "J2") (pin "6") (pinfunction "6_6") (pintype "passive"))
      (node (ref "J3") (pin "19") (pinfunction "19_19") (pintype "passive"))
      (node (ref "J3") (pin "20") (pinfunction "20_20") (pintype "passive"))
      (node (ref "J3") (pin "21") (pinfunction "21_21") (pintype "passive"))
      (node (ref "J3") (pin "22") (pinfunction "22_22") (pintype "passive"))
      (node (ref "J3") (pin "7") (pinfunction "7_7") (pintype "passive"))
      (node (ref "J3") (pin "8") (pinfunction "8_8") (pintype "passive"))
      (node (ref "J4") (pin "32") (pinfunction "32_32") (pintype "passive"))
      (node (ref "J4") (pin "7") (pinfunction "7_7") (pintype "passive"))
      (node (ref "J5") (pin "6") (pinfunction "6_6") (pintype "passive"))
      (node (ref "J5") (pin "7") (pinfunction "7_7") (pintype "passive"))
      (node (ref "J7") (pin "4") (pinfunction "4_4") (pintype "passive"))
      (node (ref "P7") (pin "A1") (pinfunction "GND_A1") (pintype "bidirectional"))
      (node (ref "P7") (pin "B1") (pinfunction "GND_B1") (pintype "bidirectional"))
      (node (ref "P9") (pin "A1") (pinfunction "GND_A1") (pintype "bidirectional"))
      (node (ref "P9") (pin "B1") (pinfunction "GND_B1") (pintype "bidirectional"))
      (node (ref "PWR") (pin "2") (pinfunction "K_2") (pintype "passive"))
      (node (ref "R10") (pin "2") (pinfunction "2_2") (pintype "passive"))
      (node (ref "R11") (pin "2") (pinfunction "2_2") (pintype "passive"))
      (node (ref "R21") (pin "1") (pinfunction "1_1") (pintype "passive"))
      (node (ref "R22") (pin "1") (pinfunction "1_1") (pintype "passive"))
      (node (ref "R8") (pin "1") (pinfunction "1_1") (pintype "passive"))
      (node (ref "R9") (pin "1") (pinfunction "1_1") (pintype "passive"))
      (node (ref "S1") (pin "3") (pinfunction "B1_3") (pintype "passive"))
      (node (ref "S2") (pin "3") (pinfunction "B1_3") (pintype "passive"))
      (node (ref "S5") (pin "2") (pinfunction "2_2") (pintype "passive"))
      (node (ref "U1") (pin "1") (pinfunction "GND_1") (pintype "passive"))
      (node (ref "U2") (pin "12") (pinfunction "VSSA_12") (pintype "power_in"))
      (node (ref "U2") (pin "18") (pinfunction "VSS_4_18") (pintype "power_in"))
      (node (ref "U2") (pin "31") (pinfunction "VSS_1_31") (pintype "power_in"))
      (node (ref "U2") (pin "63") (pinfunction "VSS_3_63") (pintype "power_in"))
      (node (ref "U3") (pin "18") (pinfunction "VSS/GND_18") (pintype "power_in"))
    )
    (net (code "86") (name "Net-(D2-K)") (class "Default")
      (node (ref "D2") (pin "2") (pinfunction "K_2") (pintype "passive"))
      (node (ref "R13") (pin "2") (pinfunction "2_2") (pintype "passive"))
    )
    (net (code "87") (name "Net-(D3-K)") (class "Default")
      (node (ref "D3") (pin "2") (pinfunction "K_2") (pintype "passive"))
      (node (ref "R21") (pin "2") (pinfunction "2_2") (pintype "passive"))
    )
    (net (code "88") (name "Net-(J3-Pad6)") (class "Default")
      (node (ref "J3") (pin "6") (pinfunction "6_6") (pintype "passive"))
      (node (ref "R5") (pin "1") (pinfunction "1_1") (pintype "passive"))
    )
    (net (code "89") (name "Net-(J3-Pad10)") (class "Default")
      (node (ref "J3") (pin "10") (pinfunction "10_10") (pintype "passive"))
      (node (ref "J5") (pin "1") (pinfunction "1_1") (pintype "passive"))
    )
    (net (code "90") (name "Net-(LED1-A)") (class "Default")
      (node (ref "LED1") (pin "1") (pinfunction "A_1") (pintype "passive"))
      (node (ref "R2") (pin "2") (pinfunction "2_2") (pintype "passive"))
    )
    (net (code "91") (name "Net-(LED2-A)") (class "Default")
      (node (ref "LED2") (pin "1") (pinfunction "A_1") (pintype "passive"))
      (node (ref "R3") (pin "2") (pinfunction "2_2") (pintype "passive"))
    )
    (net (code "92") (name "Net-(P7-CC-PadA5)") (class "Default")
      (node (ref "P7") (pin "A5") (pinfunction "CC_A5") (pintype "bidirectional"))
      (node (ref "R8") (pin "2") (pinfunction "2_2") (pintype "passive"))
    )
    (net (code "93") (name "Net-(P7-CC-PadB5)") (class "Default")
      (node (ref "P7") (pin "B5") (pinfunction "CC_B5") (pintype "bidirectional"))
      (node (ref "R9") (pin "2") (pinfunction "2_2") (pintype "passive"))
    )
    (net (code "94") (name "Net-(P9-CC-PadA5)") (class "Default")
      (node (ref "P9") (pin "A5") (pinfunction "CC_A5") (pintype "bidirectional"))
      (node (ref "R10") (pin "1") (pinfunction "1_1") (pintype "passive"))
    )
    (net (code "95") (name "Net-(P9-CC-PadB5)") (class "Default")
      (node (ref "P9") (pin "B5") (pinfunction "CC_B5") (pintype "bidirectional"))
      (node (ref "R11") (pin "1") (pinfunction "1_1") (pintype "passive"))
    )
    (net (code "96") (name "Net-(PWR-A)") (class "Default")
      (node (ref "PWR") (pin "1") (pinfunction "A_1") (pintype "passive"))
      (node (ref "R1") (pin "1") (pinfunction "1_1") (pintype "passive"))
    )
    (net (code "97") (name "Net-(U1-VOUT)") (class "Default")
      (node (ref "C13") (pin "1") (pinfunction "1_1") (pintype "passive"))
      (node (ref "S3") (pin "1") (pinfunction "1_1") (pintype "passive"))
      (node (ref "U1") (pin "2") (pinfunction "VOUT_2") (pintype "passive"))
    )
    (net (code "98") (name "Net-(U2-VDD_2)") (class "Default")
      (node (ref "R16") (pin "2") (pinfunction "2_2") (pintype "passive"))
      (node (ref "U2") (pin "48") (pinfunction "VDD_2_48") (pintype "power_in"))
    )
    (net (code "99") (name "Net-(U2-VSS_2)") (class "Default")
      (node (ref "R22") (pin "2") (pinfunction "2_2") (pintype "passive"))
      (node (ref "U2") (pin "47") (pinfunction "VSS_2_47") (pintype "power_in"))
    )
    (net (code "100") (name "unconnected-(P7-RFU1-PadA8)") (class "Default")
      (node (ref "P7") (pin "A8") (pinfunction "RFU1_A8") (pintype "bidirectional+no_connect"))
    )
    (net (code "101") (name "unconnected-(P7-RFU1-PadB8)") (class "Default")
      (node (ref "P7") (pin "B8") (pinfunction "RFU1_B8") (pintype "bidirectional+no_connect"))
    )
    (net (code "102") (name "unconnected-(P9-RFU1-PadA8)") (class "Default")
      (node (ref "P9") (pin "A8") (pinfunction "RFU1_A8") (pintype "bidirectional+no_connect"))
    )
    (net (code "103") (name "unconnected-(P9-RFU1-PadB8)") (class "Default")
      (node (ref "P9") (pin "B8") (pinfunction "RFU1_B8") (pintype "bidirectional+no_connect"))
    )
    (net (code "104") (name "unconnected-(S1-A1-Pad4)") (class "Default")
      (node (ref "S1") (pin "4") (pinfunction "A1_4") (pintype "passive"))
    )
    (net (code "105") (name "unconnected-(S1-B0-Pad2)") (class "Default")
      (node (ref "S1") (pin "2") (pinfunction "B0_2") (pintype "passive"))
    )
    (net (code "106") (name "unconnected-(S2-A1-Pad4)") (class "Default")
      (node (ref "S2") (pin "4") (pinfunction "A1_4") (pintype "passive"))
    )
    (net (code "107") (name "unconnected-(S2-B0-Pad2)") (class "Default")
      (node (ref "S2") (pin "2") (pinfunction "B0_2") (pintype "passive"))
    )
    (net (code "108") (name "unconnected-(S3-Pad2)") (class "Default")
      (node (ref "S3") (pin "2") (pinfunction "2_2") (pintype "passive"))
    )
    (net (code "109") (name "unconnected-(U3-PA5{slash}UART1_CTS{slash}PA1_(no5V)-Pad2)") (class "Default")
      (node (ref "U3") (pin "2") (pinfunction "PA5/UART1_CTS/PA1_(no5V)_2") (pintype "bidirectional+no_connect"))
    )
    (net (code "110") (name "unconnected-(U3-PB12{slash}SPI2_NSS{slash}CAN2_RX-Pad5)") (class "Default")
      (node (ref "U3") (pin "5") (pinfunction "PB12/SPI2_NSS/CAN2_RX_5") (pintype "bidirectional+no_connect"))
    )
    (net (code "111") (name "unconnected-(U3-PB14{slash}SPI2_MISO{slash}UART3_RTS-Pad7)") (class "Default")
      (node (ref "U3") (pin "7") (pinfunction "PB14/SPI2_MISO/UART3_RTS_7") (pintype "bidirectional+no_connect"))
    )
    (net (code "112") (name "unconnected-(U3-PB15{slash}SPI2_MOSI{slash}UART1_TX-Pad8)") (class "Default")
      (node (ref "U3") (pin "8") (pinfunction "PB15/SPI2_MOSI/UART1_TX_8") (pintype "bidirectional+no_connect"))
    )
  )
)
